# SpaStroWi_V1_R0.net
KiCad netlist of a schematic drawn in EAGLE
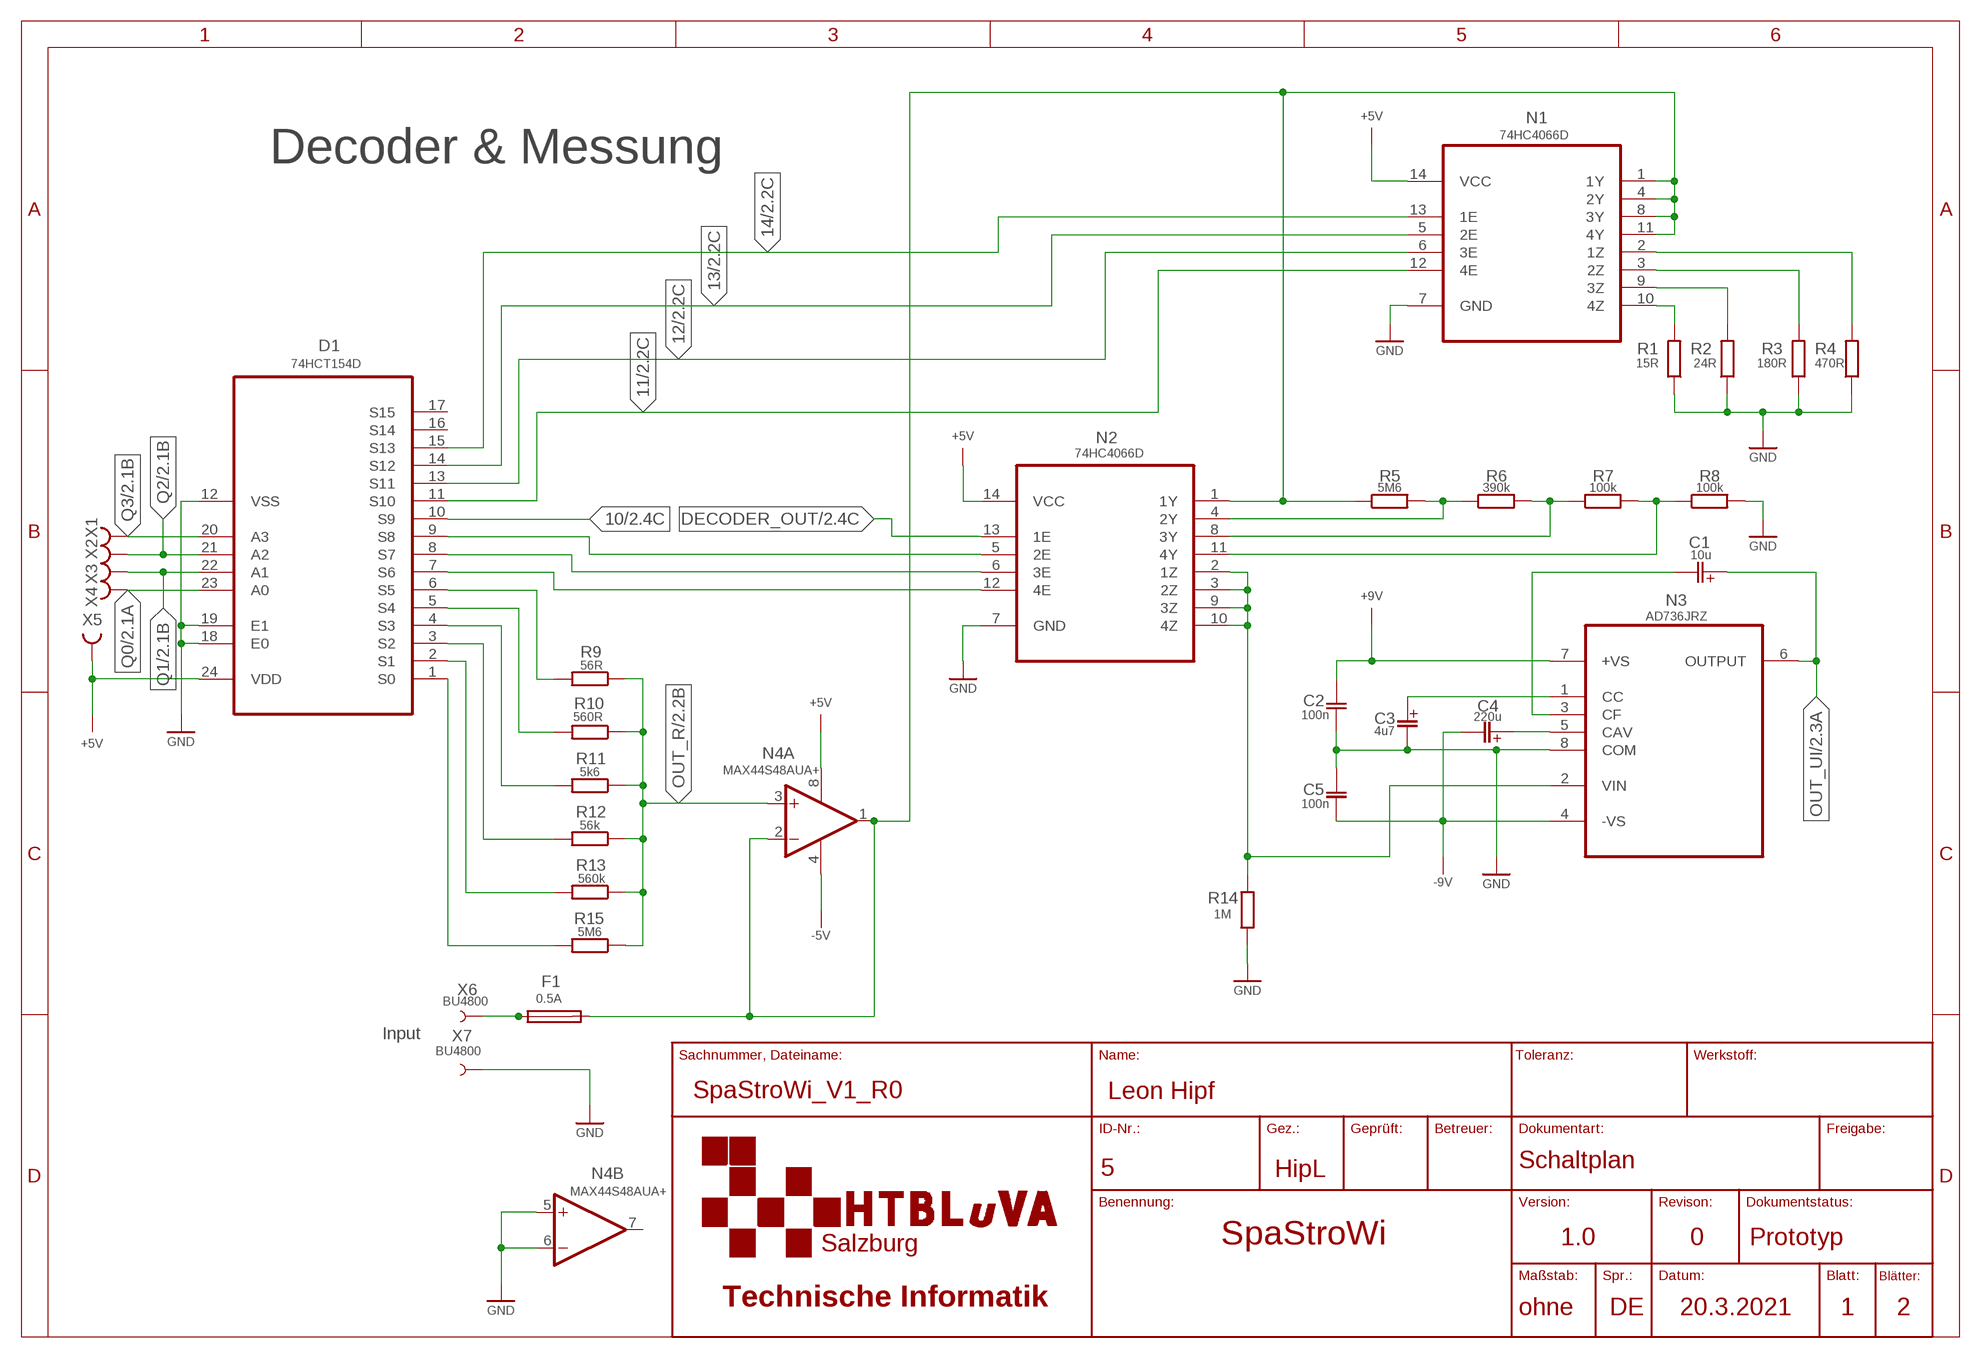
[diagram p0: schematic, sheet 1]
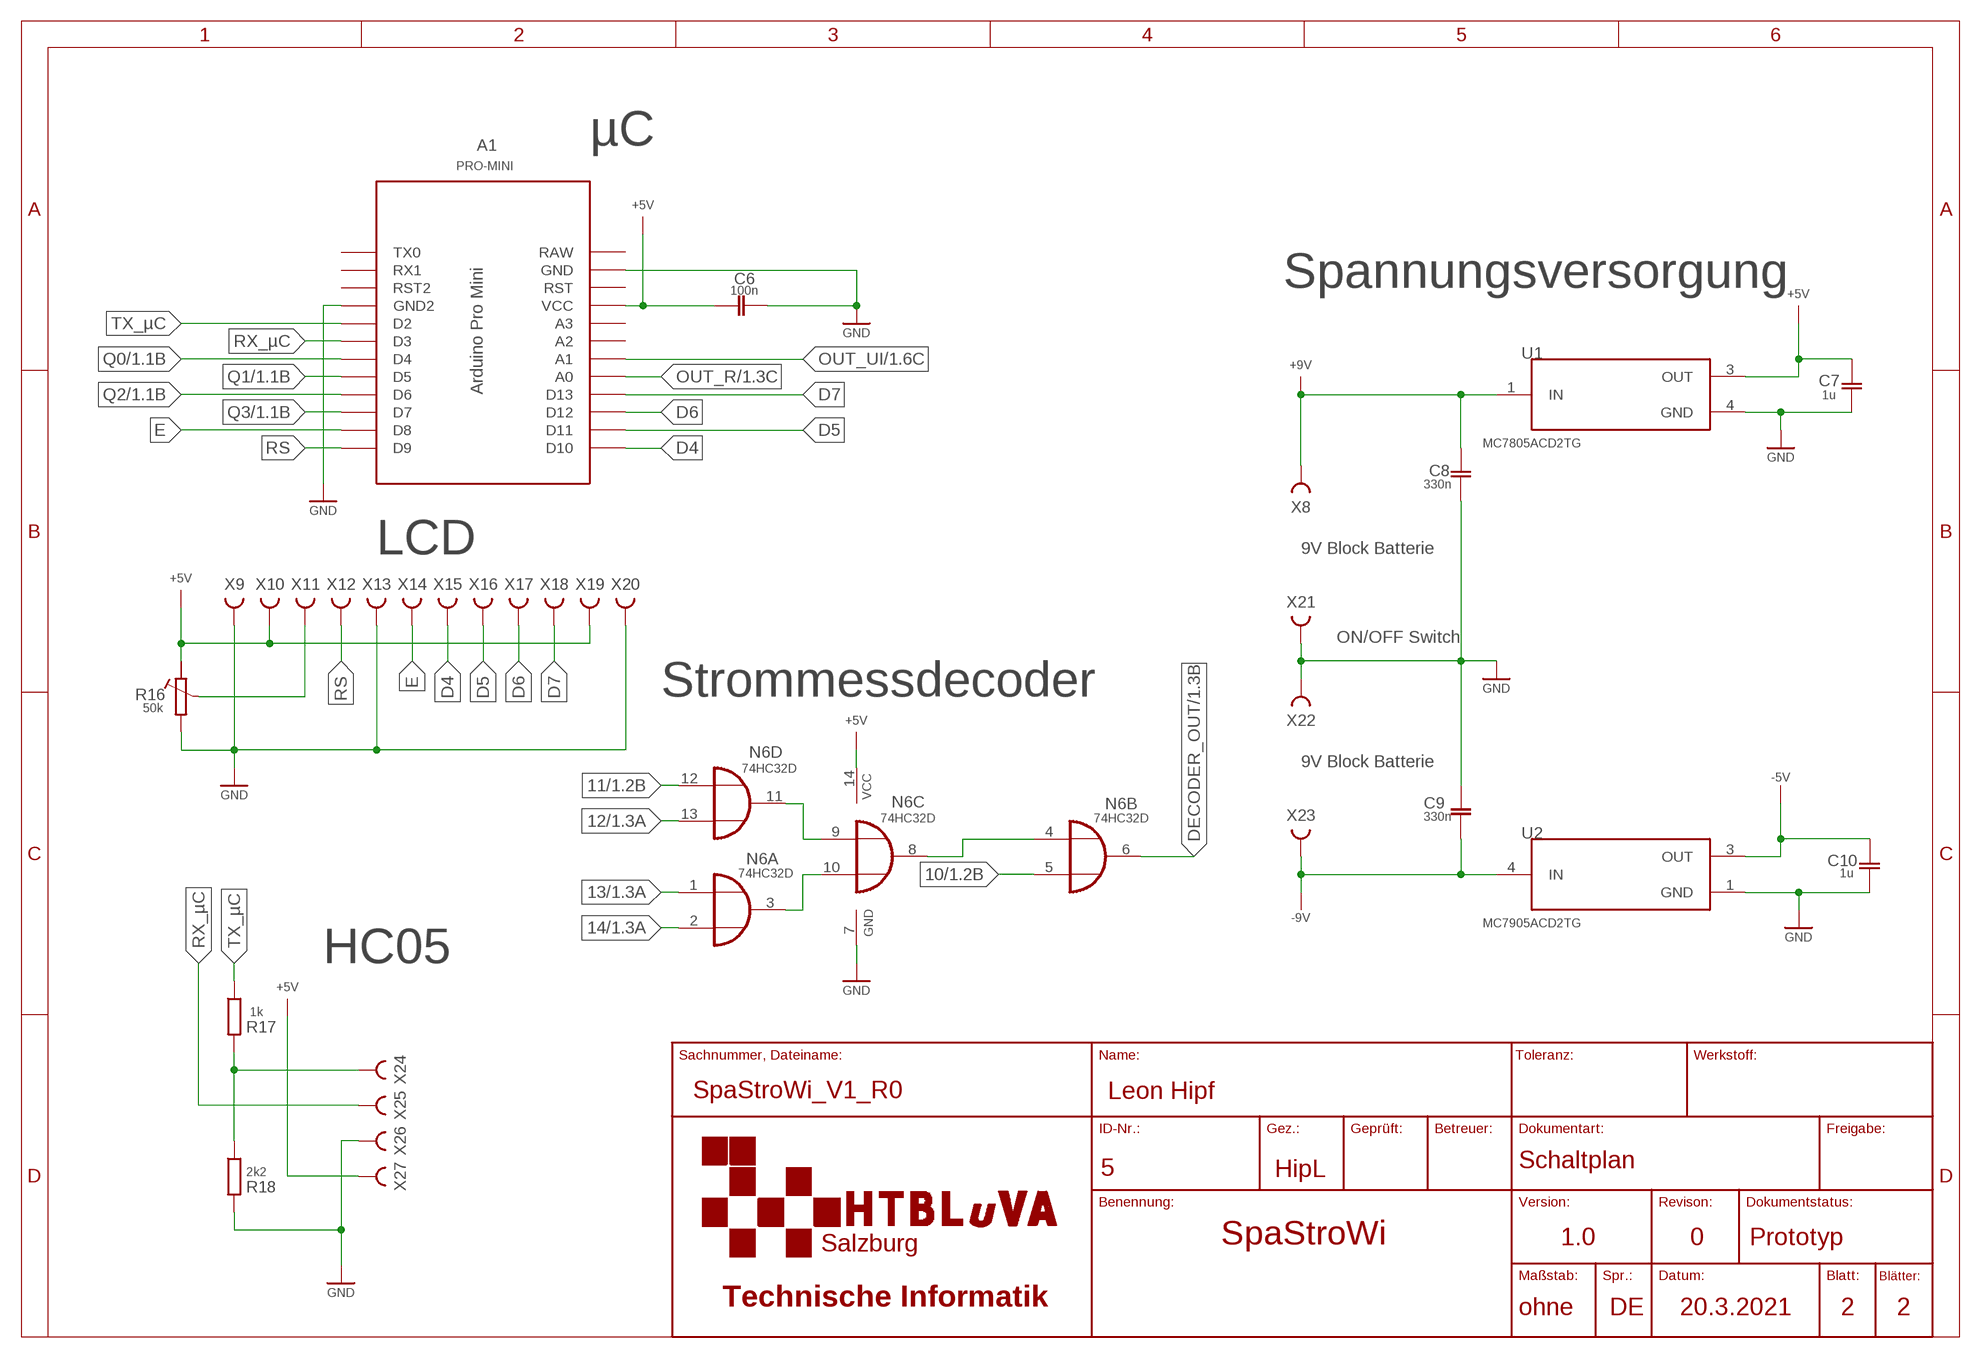
[diagram p1: schematic, sheet 2]

(export (version "E")
  (design (tool "Eeschema 10.0.6"))
  (components
    (comp (ref "C1")
      (value "10u")
      (footprint "eagle-import:153CLV-0405")
      (libsource (lib "eagle-import") (part "CPOL-EU153CLV-0405"))
    )
    (comp (ref "C2")
      (value "100n")
      (footprint "eagle-import:C0805")
      (libsource (lib "eagle-import") (part "C-EUC0805"))
    )
    (comp (ref "C3")
      (value "4u7")
      (footprint "eagle-import:153CLV-0405")
      (libsource (lib "eagle-import") (part "CPOL-EU153CLV-0405"))
    )
    (comp (ref "C4")
      (value "220u")
      (footprint "eagle-import:153CLV-0405")
      (libsource (lib "eagle-import") (part "CPOL-EU153CLV-0405"))
    )
    (comp (ref "C5")
      (value "100n")
      (footprint "eagle-import:C0805")
      (libsource (lib "eagle-import") (part "C-EUC0805"))
    )
    (comp (ref "D1")
      (value "74HCT154D")
      (footprint "eagle-import:SOIC127P1030X265-24N")
      (libsource (lib "eagle-import") (part "74HCT154D"))
    )
    (comp (ref "F1")
      (value "0.5A")
      (footprint "eagle-import:354-0101ZXGY")
      (libsource (lib "eagle-import") (part "0.5A"))
    )
    (comp (ref "N1")
      (value "74HC4066D")
      (footprint "eagle-import:SOIC127P600X175-14N")
      (fields (field (name "MF") "Nexperia") (field (name "MP") "74HC4066D,653"))
      (libsource (lib "eagle-import") (part "74HC4066D,653"))
    )
    (comp (ref "N2")
      (value "74HC4066D")
      (footprint "eagle-import:SOIC127P600X175-14N")
      (fields (field (name "MF") "Nexperia") (field (name "MP") "74HC4066D,653"))
      (libsource (lib "eagle-import") (part "74HC4066D,653"))
    )
    (comp (ref "N3")
      (value "AD736JRZ")
      (footprint "eagle-import:DIP794W45P254L959H508Q8")
      (libsource (lib "eagle-import") (part "AD736JRZ_THT"))
    )
    (comp (ref "N4")
      (value "MAX44S48AUA+")
      (footprint "eagle-import:SOP65P490X110-8N")
      (libsource (lib "eagle-import") (part "MAX44S48AUA+"))
    )
    (comp (ref "R1")
      (value "15R")
      (footprint "eagle-import:R2010")
      (libsource (lib "eagle-import") (part "R-EU_R2010"))
    )
    (comp (ref "R2")
      (value "24R")
      (footprint "eagle-import:R2512")
      (libsource (lib "eagle-import") (part "R-EU_R2512"))
    )
    (comp (ref "R3")
      (value "180R")
      (footprint "eagle-import:R0402")
      (libsource (lib "eagle-import") (part "R-EU_R0402"))
    )
    (comp (ref "R4")
      (value "470R")
      (footprint "eagle-import:R0805")
      (libsource (lib "eagle-import") (part "R-EU_R0805"))
    )
    (comp (ref "R5")
      (value "5M6")
      (footprint "eagle-import:R0805")
      (libsource (lib "eagle-import") (part "R-EU_R0805"))
    )
    (comp (ref "R6")
      (value "390k")
      (footprint "eagle-import:R0805")
      (libsource (lib "eagle-import") (part "R-EU_R0805"))
    )
    (comp (ref "R7")
      (value "100k")
      (footprint "eagle-import:R0805")
      (libsource (lib "eagle-import") (part "R-EU_R0805"))
    )
    (comp (ref "R8")
      (value "100k")
      (footprint "eagle-import:R0805")
      (libsource (lib "eagle-import") (part "R-EU_R0805"))
    )
    (comp (ref "R9")
      (value "56R")
      (footprint "eagle-import:R0805")
      (libsource (lib "eagle-import") (part "R-EU_R0805"))
    )
    (comp (ref "R10")
      (value "560R")
      (footprint "eagle-import:R0805")
      (libsource (lib "eagle-import") (part "R-EU_R0805"))
    )
    (comp (ref "R11")
      (value "5k6")
      (footprint "eagle-import:R0805")
      (libsource (lib "eagle-import") (part "R-EU_R0805"))
    )
    (comp (ref "R12")
      (value "56k")
      (footprint "eagle-import:R0805")
      (libsource (lib "eagle-import") (part "R-EU_R0805"))
    )
    (comp (ref "R13")
      (value "560k")
      (footprint "eagle-import:R0805")
      (libsource (lib "eagle-import") (part "R-EU_R0805"))
    )
    (comp (ref "R14")
      (value "1M")
      (footprint "eagle-import:R0805")
      (libsource (lib "eagle-import") (part "R-EU_R0805"))
    )
    (comp (ref "R15")
      (value "5M6")
      (footprint "eagle-import:R0805")
      (libsource (lib "eagle-import") (part "R-EU_R0805"))
    )
    (comp (ref "X1")
      (value "BUCHSE-V_0.8MM")
      (footprint "eagle-import:LSP08")
      (libsource (lib "eagle-import") (part "BUCHSE-V_0.8MM"))
    )
    (comp (ref "X2")
      (value "BUCHSE-V_0.8MM")
      (footprint "eagle-import:LSP08")
      (libsource (lib "eagle-import") (part "BUCHSE-V_0.8MM"))
    )
    (comp (ref "X3")
      (value "BUCHSE-V_0.8MM")
      (footprint "eagle-import:LSP08")
      (libsource (lib "eagle-import") (part "BUCHSE-V_0.8MM"))
    )
    (comp (ref "X4")
      (value "BUCHSE-V_0.8MM")
      (footprint "eagle-import:LSP08")
      (libsource (lib "eagle-import") (part "BUCHSE-V_0.8MM"))
    )
    (comp (ref "X5")
      (value "BUCHSE-V_0.8MM")
      (footprint "eagle-import:LSP08")
      (libsource (lib "eagle-import") (part "BUCHSE-V_0.8MM"))
    )
    (comp (ref "X6")
      (value "BU4800")
      (footprint "eagle-import:BU4800")
      (libsource (lib "eagle-import") (part "BU4800"))
    )
    (comp (ref "X7")
      (value "BU4800")
      (footprint "eagle-import:BU4800")
      (libsource (lib "eagle-import") (part "BU4800"))
    )
    (comp (ref "A1")
      (value "PRO-MINI")
      (footprint "eagle-import:PRO-MINI")
      (libsource (lib "eagle-import") (part "PRO-MINI"))
    )
    (comp (ref "C6")
      (value "100n")
      (footprint "eagle-import:C0805")
      (libsource (lib "eagle-import") (part "C-EUC0805"))
    )
    (comp (ref "C7")
      (value "1u")
      (footprint "eagle-import:C0805")
      (libsource (lib "eagle-import") (part "C-EUC0805"))
    )
    (comp (ref "C8")
      (value "330n")
      (footprint "eagle-import:C0805")
      (libsource (lib "eagle-import") (part "C-EUC0805"))
    )
    (comp (ref "C9")
      (value "330n")
      (footprint "eagle-import:C0805")
      (libsource (lib "eagle-import") (part "C-EUC0805"))
    )
    (comp (ref "C10")
      (value "1u")
      (footprint "eagle-import:C0805")
      (libsource (lib "eagle-import") (part "C-EUC0805"))
    )
    (comp (ref "N6")
      (value "74HC32D")
      (footprint "eagle-import:SO14")
      (libsource (lib "eagle-import") (part "7432DHC"))
    )
    (comp (ref "R16")
      (value "50k")
      (footprint "eagle-import:PTV09")
      (libsource (lib "eagle-import") (part "R-TRIMMPTV09"))
    )
    (comp (ref "R17")
      (value "1k")
      (footprint "eagle-import:R0805")
      (libsource (lib "eagle-import") (part "R-EU_R0805"))
    )
    (comp (ref "R18")
      (value "2k2")
      (footprint "eagle-import:R0805")
      (libsource (lib "eagle-import") (part "R-EU_R0805"))
    )
    (comp (ref "U1")
      (value "MC7805ACD2TG")
      (footprint "eagle-import:TO254P1420X457-3N")
      (fields (field (name "MF") "ON Semiconductor"))
      (libsource (lib "eagle-import") (part "MC7805ACD2TG"))
    )
    (comp (ref "U2")
      (value "MC7905ACD2TG")
      (footprint "eagle-import:TO254P1420X457-3N")
      (fields (field (name "MF") "ON Semiconductor") (field (name "MP") "MC7805ACD2TG"))
      (libsource (lib "eagle-import") (part "MC7905ACD2TG"))
    )
    (comp (ref "X8")
      (value "BUCHSE-V_0.8MM")
      (footprint "eagle-import:LSP08")
      (libsource (lib "eagle-import") (part "BUCHSE-V_0.8MM"))
    )
    (comp (ref "X9")
      (value "BUCHSE-V_0.8MM")
      (footprint "eagle-import:LSP08")
      (libsource (lib "eagle-import") (part "BUCHSE-V_0.8MM"))
    )
    (comp (ref "X10")
      (value "BUCHSE-V_0.8MM")
      (footprint "eagle-import:LSP08")
      (libsource (lib "eagle-import") (part "BUCHSE-V_0.8MM"))
    )
    (comp (ref "X11")
      (value "BUCHSE-V_0.8MM")
      (footprint "eagle-import:LSP08")
      (libsource (lib "eagle-import") (part "BUCHSE-V_0.8MM"))
    )
    (comp (ref "X12")
      (value "BUCHSE-V_0.8MM")
      (footprint "eagle-import:LSP08")
      (libsource (lib "eagle-import") (part "BUCHSE-V_0.8MM"))
    )
    (comp (ref "X13")
      (value "BUCHSE-V_0.8MM")
      (footprint "eagle-import:LSP08")
      (libsource (lib "eagle-import") (part "BUCHSE-V_0.8MM"))
    )
    (comp (ref "X14")
      (value "BUCHSE-V_0.8MM")
      (footprint "eagle-import:LSP08")
      (libsource (lib "eagle-import") (part "BUCHSE-V_0.8MM"))
    )
    (comp (ref "X15")
      (value "BUCHSE-V_0.8MM")
      (footprint "eagle-import:LSP08")
      (libsource (lib "eagle-import") (part "BUCHSE-V_0.8MM"))
    )
    (comp (ref "X16")
      (value "BUCHSE-V_0.8MM")
      (footprint "eagle-import:LSP08")
      (libsource (lib "eagle-import") (part "BUCHSE-V_0.8MM"))
    )
    (comp (ref "X17")
      (value "BUCHSE-V_0.8MM")
      (footprint "eagle-import:LSP08")
      (libsource (lib "eagle-import") (part "BUCHSE-V_0.8MM"))
    )
    (comp (ref "X18")
      (value "BUCHSE-V_0.8MM")
      (footprint "eagle-import:LSP08")
      (libsource (lib "eagle-import") (part "BUCHSE-V_0.8MM"))
    )
    (comp (ref "X19")
      (value "BUCHSE-V_0.8MM")
      (footprint "eagle-import:LSP08")
      (libsource (lib "eagle-import") (part "BUCHSE-V_0.8MM"))
    )
    (comp (ref "X20")
      (value "BUCHSE-V_0.8MM")
      (footprint "eagle-import:LSP08")
      (libsource (lib "eagle-import") (part "BUCHSE-V_0.8MM"))
    )
    (comp (ref "X21")
      (value "BUCHSE-V_0.8MM")
      (footprint "eagle-import:LSP08")
      (libsource (lib "eagle-import") (part "BUCHSE-V_0.8MM"))
    )
    (comp (ref "X22")
      (value "BUCHSE-V_0.8MM")
      (footprint "eagle-import:LSP08")
      (libsource (lib "eagle-import") (part "BUCHSE-V_0.8MM"))
    )
    (comp (ref "X23")
      (value "BUCHSE-V_0.8MM")
      (footprint "eagle-import:LSP08")
      (libsource (lib "eagle-import") (part "BUCHSE-V_0.8MM"))
    )
    (comp (ref "X24")
      (value "BUCHSE-V_0.8MM")
      (footprint "eagle-import:LSP08")
      (libsource (lib "eagle-import") (part "BUCHSE-V_0.8MM"))
    )
    (comp (ref "X25")
      (value "BUCHSE-V_0.8MM")
      (footprint "eagle-import:LSP08")
      (libsource (lib "eagle-import") (part "BUCHSE-V_0.8MM"))
    )
    (comp (ref "X26")
      (value "BUCHSE-V_0.8MM")
      (footprint "eagle-import:LSP08")
      (libsource (lib "eagle-import") (part "BUCHSE-V_0.8MM"))
    )
    (comp (ref "X27")
      (value "BUCHSE-V_0.8MM")
      (footprint "eagle-import:LSP08")
      (libsource (lib "eagle-import") (part "BUCHSE-V_0.8MM"))
    )
  )
  (nets
    (net (code "1") (name "+5V") (class "Default")
      (node (ref "A1") (pin "VCC") (pinfunction "VCC_VCC") (pintype "bidirectional"))
      (node (ref "C6") (pin "1") (pinfunction "1_1") (pintype "passive"))
      (node (ref "C7") (pin "1") (pinfunction "1_1") (pintype "passive"))
      (node (ref "D1") (pin "24") (pinfunction "VDD_24") (pintype "power_in"))
      (node (ref "N1") (pin "14") (pinfunction "VCC_14") (pintype "power_in"))
      (node (ref "N2") (pin "14") (pinfunction "VCC_14") (pintype "power_in"))
      (node (ref "N4") (pin "8") (pinfunction "VCC+_8") (pintype "power_in"))
      (node (ref "N6") (pin "14") (pinfunction "VCC_14") (pintype "power_in"))
      (node (ref "R16") (pin "1") (pinfunction "E_1") (pintype "passive"))
      (node (ref "U1") (pin "3") (pinfunction "OUT_3") (pintype "power_in"))
      (node (ref "X10") (pin "MP") (pinfunction "MP_MP") (pintype "passive"))
      (node (ref "X19") (pin "MP") (pinfunction "MP_MP") (pintype "passive"))
      (node (ref "X27") (pin "MP") (pinfunction "MP_MP") (pintype "passive"))
      (node (ref "X5") (pin "MP") (pinfunction "MP_MP") (pintype "passive"))
    )
    (net (code "2") (name "+9V") (class "Default")
      (node (ref "C2") (pin "1") (pinfunction "1_1") (pintype "passive"))
      (node (ref "C8") (pin "2") (pinfunction "2_2") (pintype "passive"))
      (node (ref "N3") (pin "7") (pinfunction "+VS_7") (pintype "power_in"))
      (node (ref "U1") (pin "1") (pinfunction "IN_1") (pintype "input"))
      (node (ref "X8") (pin "MP") (pinfunction "MP_MP") (pintype "passive"))
    )
    (net (code "3") (name "-5V") (class "Default")
      (node (ref "C10") (pin "1") (pinfunction "1_1") (pintype "passive"))
      (node (ref "N4") (pin "4") (pinfunction "VCC-_4") (pintype "power_in"))
      (node (ref "U2") (pin "3") (pinfunction "OUT_3") (pintype "power_in"))
    )
    (net (code "4") (name "-9V") (class "Default")
      (node (ref "C4") (pin "-") (pinfunction "-_-") (pintype "passive"))
      (node (ref "C5") (pin "2") (pinfunction "2_2") (pintype "passive"))
      (node (ref "C9") (pin "1") (pinfunction "1_1") (pintype "passive"))
      (node (ref "N3") (pin "4") (pinfunction "-VS_4") (pintype "power_in"))
      (node (ref "U2") (pin "4") (pinfunction "IN_4") (pintype "input"))
      (node (ref "X23") (pin "MP") (pinfunction "MP_MP") (pintype "passive"))
    )
    (net (code "5") (name "10") (class "Default")
      (node (ref "D1") (pin "10") (pinfunction "S9_10") (pintype "output"))
      (node (ref "N6") (pin "5") (pinfunction "I1_5") (pintype "input"))
    )
    (net (code "6") (name "11") (class "Default")
      (node (ref "D1") (pin "11") (pinfunction "S10_11") (pintype "output"))
      (node (ref "N1") (pin "12") (pinfunction "4E_12") (pintype "input"))
      (node (ref "N6") (pin "12") (pinfunction "I0_12") (pintype "input"))
    )
    (net (code "7") (name "12") (class "Default")
      (node (ref "D1") (pin "13") (pinfunction "S11_13") (pintype "output"))
      (node (ref "N1") (pin "6") (pinfunction "3E_6") (pintype "input"))
      (node (ref "N6") (pin "13") (pinfunction "I1_13") (pintype "input"))
    )
    (net (code "8") (name "13") (class "Default")
      (node (ref "D1") (pin "14") (pinfunction "S12_14") (pintype "output"))
      (node (ref "N1") (pin "5") (pinfunction "2E_5") (pintype "input"))
      (node (ref "N6") (pin "1") (pinfunction "I0_1") (pintype "input"))
    )
    (net (code "9") (name "14") (class "Default")
      (node (ref "D1") (pin "15") (pinfunction "S13_15") (pintype "output"))
      (node (ref "N1") (pin "13") (pinfunction "1E_13") (pintype "input"))
      (node (ref "N6") (pin "2") (pinfunction "I1_2") (pintype "input"))
    )
    (net (code "10") (name "D4") (class "Default")
      (node (ref "A1") (pin "D10") (pinfunction "D10_D10") (pintype "bidirectional"))
      (node (ref "X15") (pin "MP") (pinfunction "MP_MP") (pintype "passive"))
    )
    (net (code "11") (name "D5") (class "Default")
      (node (ref "A1") (pin "D11") (pinfunction "D11_D11") (pintype "bidirectional"))
      (node (ref "X16") (pin "MP") (pinfunction "MP_MP") (pintype "passive"))
    )
    (net (code "12") (name "D6") (class "Default")
      (node (ref "A1") (pin "D12") (pinfunction "D12_D12") (pintype "bidirectional"))
      (node (ref "X17") (pin "MP") (pinfunction "MP_MP") (pintype "passive"))
    )
    (net (code "13") (name "D7") (class "Default")
      (node (ref "A1") (pin "D13") (pinfunction "D13_D13") (pintype "bidirectional"))
      (node (ref "X18") (pin "MP") (pinfunction "MP_MP") (pintype "passive"))
    )
    (net (code "14") (name "DECODER_OUT") (class "Default")
      (node (ref "N2") (pin "13") (pinfunction "1E_13") (pintype "input"))
      (node (ref "N6") (pin "6") (pinfunction "O_6") (pintype "output"))
    )
    (net (code "15") (name "E") (class "Default")
      (node (ref "A1") (pin "D8") (pinfunction "D8_D8") (pintype "bidirectional"))
      (node (ref "X14") (pin "MP") (pinfunction "MP_MP") (pintype "passive"))
    )
    (net (code "16") (name "GND") (class "Default")
      (node (ref "A1") (pin "GND") (pinfunction "GND_GND") (pintype "input"))
      (node (ref "A1") (pin "GND1") (pinfunction "GND2_GND1") (pintype "bidirectional"))
      (node (ref "C10") (pin "2") (pinfunction "2_2") (pintype "passive"))
      (node (ref "C2") (pin "2") (pinfunction "2_2") (pintype "passive"))
      (node (ref "C3") (pin "-") (pinfunction "-_-") (pintype "passive"))
      (node (ref "C5") (pin "1") (pinfunction "1_1") (pintype "passive"))
      (node (ref "C6") (pin "2") (pinfunction "2_2") (pintype "passive"))
      (node (ref "C7") (pin "2") (pinfunction "2_2") (pintype "passive"))
      (node (ref "C8") (pin "1") (pinfunction "1_1") (pintype "passive"))
      (node (ref "C9") (pin "2") (pinfunction "2_2") (pintype "passive"))
      (node (ref "D1") (pin "12") (pinfunction "VSS_12") (pintype "power_in"))
      (node (ref "D1") (pin "18") (pinfunction "E0_18") (pintype "input"))
      (node (ref "D1") (pin "19") (pinfunction "E1_19") (pintype "input"))
      (node (ref "N1") (pin "7") (pinfunction "GND_7") (pintype "passive"))
      (node (ref "N2") (pin "7") (pinfunction "GND_7") (pintype "passive"))
      (node (ref "N3") (pin "8") (pinfunction "COM_8") (pintype "passive"))
      (node (ref "N4") (pin "5") (pinfunction "NON-INVERTING_INPUT2_5") (pintype "input"))
      (node (ref "N4") (pin "6") (pinfunction "INVERTING_INPUT2_6") (pintype "input"))
      (node (ref "N6") (pin "7") (pinfunction "GND_7") (pintype "power_in"))
      (node (ref "R1") (pin "1") (pinfunction "1_1") (pintype "passive"))
      (node (ref "R14") (pin "1") (pinfunction "1_1") (pintype "passive"))
      (node (ref "R16") (pin "3") (pinfunction "A_3") (pintype "passive"))
      (node (ref "R18") (pin "2") (pinfunction "2_2") (pintype "passive"))
      (node (ref "R2") (pin "1") (pinfunction "1_1") (pintype "passive"))
      (node (ref "R3") (pin "1") (pinfunction "1_1") (pintype "passive"))
      (node (ref "R4") (pin "1") (pinfunction "1_1") (pintype "passive"))
      (node (ref "R8") (pin "2") (pinfunction "2_2") (pintype "passive"))
      (node (ref "U1") (pin "4") (pinfunction "GND_4") (pintype "power_in"))
      (node (ref "U2") (pin "1") (pinfunction "GND_1") (pintype "power_in"))
      (node (ref "X13") (pin "MP") (pinfunction "MP_MP") (pintype "passive"))
      (node (ref "X20") (pin "MP") (pinfunction "MP_MP") (pintype "passive"))
      (node (ref "X21") (pin "MP") (pinfunction "MP_MP") (pintype "passive"))
      (node (ref "X22") (pin "MP") (pinfunction "MP_MP") (pintype "passive"))
      (node (ref "X26") (pin "MP") (pinfunction "MP_MP") (pintype "passive"))
      (node (ref "X7") (pin "P$1") (pinfunction "KL_P$1") (pintype "passive"))
      (node (ref "X9") (pin "MP") (pinfunction "MP_MP") (pintype "passive"))
    )
    (net (code "17") (name "Net-(D1-S0)") (class "Default")
      (node (ref "D1") (pin "1") (pinfunction "S0_1") (pintype "output"))
      (node (ref "R15") (pin "2") (pinfunction "2_2") (pintype "passive"))
    )
    (net (code "18") (name "Net-(D1-S1)") (class "Default")
      (node (ref "D1") (pin "2") (pinfunction "S1_2") (pintype "output"))
      (node (ref "R13") (pin "2") (pinfunction "2_2") (pintype "passive"))
    )
    (net (code "19") (name "Net-(D1-S2)") (class "Default")
      (node (ref "D1") (pin "3") (pinfunction "S2_3") (pintype "output"))
      (node (ref "R12") (pin "2") (pinfunction "2_2") (pintype "passive"))
    )
    (net (code "20") (name "Net-(D1-S3)") (class "Default")
      (node (ref "D1") (pin "4") (pinfunction "S3_4") (pintype "output"))
      (node (ref "R11") (pin "2") (pinfunction "2_2") (pintype "passive"))
    )
    (net (code "21") (name "Net-(D1-S4)") (class "Default")
      (node (ref "D1") (pin "5") (pinfunction "S4_5") (pintype "output"))
      (node (ref "R10") (pin "2") (pinfunction "2_2") (pintype "passive"))
    )
    (net (code "22") (name "Net-(D1-S5)") (class "Default")
      (node (ref "D1") (pin "6") (pinfunction "S5_6") (pintype "output"))
      (node (ref "R9") (pin "2") (pinfunction "2_2") (pintype "passive"))
    )
    (net (code "23") (name "Net-(D1-S6)") (class "Default")
      (node (ref "D1") (pin "7") (pinfunction "S6_7") (pintype "output"))
      (node (ref "N2") (pin "12") (pinfunction "4E_12") (pintype "input"))
    )
    (net (code "24") (name "Net-(D1-S7)") (class "Default")
      (node (ref "D1") (pin "8") (pinfunction "S7_8") (pintype "output"))
      (node (ref "N2") (pin "6") (pinfunction "3E_6") (pintype "input"))
    )
    (net (code "25") (name "Net-(D1-S8)") (class "Default")
      (node (ref "D1") (pin "9") (pinfunction "S8_9") (pintype "output"))
      (node (ref "N2") (pin "5") (pinfunction "2E_5") (pintype "input"))
    )
    (net (code "26") (name "Net-(N1-1Y)") (class "Default")
      (node (ref "F1") (pin "2") (pinfunction "2_2") (pintype "passive"))
      (node (ref "N1") (pin "1") (pinfunction "1Y_1") (pintype "bidirectional"))
      (node (ref "N1") (pin "11") (pinfunction "4Y_11") (pintype "bidirectional"))
      (node (ref "N1") (pin "4") (pinfunction "2Y_4") (pintype "bidirectional"))
      (node (ref "N1") (pin "8") (pinfunction "3Y_8") (pintype "bidirectional"))
      (node (ref "N2") (pin "1") (pinfunction "1Y_1") (pintype "bidirectional"))
      (node (ref "N4") (pin "1") (pinfunction "OUTPUT1_1") (pintype "output"))
      (node (ref "N4") (pin "2") (pinfunction "INVERTING_INPUT1_2") (pintype "input"))
      (node (ref "R5") (pin "1") (pinfunction "1_1") (pintype "passive"))
    )
    (net (code "27") (name "Net-(N1-1Z)") (class "Default")
      (node (ref "N1") (pin "2") (pinfunction "1Z_2") (pintype "bidirectional"))
      (node (ref "R4") (pin "2") (pinfunction "2_2") (pintype "passive"))
    )
    (net (code "28") (name "Net-(N1-2Z)") (class "Default")
      (node (ref "N1") (pin "3") (pinfunction "2Z_3") (pintype "bidirectional"))
      (node (ref "R3") (pin "2") (pinfunction "2_2") (pintype "passive"))
    )
    (net (code "29") (name "Net-(N1-3Z)") (class "Default")
      (node (ref "N1") (pin "9") (pinfunction "3Z_9") (pintype "bidirectional"))
      (node (ref "R2") (pin "2") (pinfunction "2_2") (pintype "passive"))
    )
    (net (code "30") (name "Net-(N1-4Z)") (class "Default")
      (node (ref "N1") (pin "10") (pinfunction "4Z_10") (pintype "bidirectional"))
      (node (ref "R1") (pin "2") (pinfunction "2_2") (pintype "passive"))
    )
    (net (code "31") (name "Net-(N2-1Z)") (class "Default")
      (node (ref "N2") (pin "10") (pinfunction "4Z_10") (pintype "bidirectional"))
      (node (ref "N2") (pin "2") (pinfunction "1Z_2") (pintype "bidirectional"))
      (node (ref "N2") (pin "3") (pinfunction "2Z_3") (pintype "bidirectional"))
      (node (ref "N2") (pin "9") (pinfunction "3Z_9") (pintype "bidirectional"))
      (node (ref "N3") (pin "2") (pinfunction "VIN_2") (pintype "input"))
      (node (ref "R14") (pin "2") (pinfunction "2_2") (pintype "passive"))
    )
    (net (code "32") (name "Net-(N2-2Y)") (class "Default")
      (node (ref "N2") (pin "4") (pinfunction "2Y_4") (pintype "bidirectional"))
      (node (ref "R5") (pin "2") (pinfunction "2_2") (pintype "passive"))
      (node (ref "R6") (pin "1") (pinfunction "1_1") (pintype "passive"))
    )
    (net (code "33") (name "Net-(N2-3Y)") (class "Default")
      (node (ref "N2") (pin "8") (pinfunction "3Y_8") (pintype "bidirectional"))
      (node (ref "R6") (pin "2") (pinfunction "2_2") (pintype "passive"))
      (node (ref "R7") (pin "1") (pinfunction "1_1") (pintype "passive"))
    )
    (net (code "34") (name "Net-(N2-4Y)") (class "Default")
      (node (ref "N2") (pin "11") (pinfunction "4Y_11") (pintype "bidirectional"))
      (node (ref "R7") (pin "2") (pinfunction "2_2") (pintype "passive"))
      (node (ref "R8") (pin "1") (pinfunction "1_1") (pintype "passive"))
    )
    (net (code "35") (name "Net-(N3-CAV)") (class "Default")
      (node (ref "C4") (pin "+") (pinfunction "+_+") (pintype "passive"))
      (node (ref "N3") (pin "5") (pinfunction "CAV_5") (pintype "passive"))
    )
    (net (code "36") (name "Net-(N3-CC)") (class "Default")
      (node (ref "C3") (pin "+") (pinfunction "+_+") (pintype "passive"))
      (node (ref "N3") (pin "1") (pinfunction "CC_1") (pintype "passive"))
    )
    (net (code "37") (name "Net-(N3-CF)") (class "Default")
      (node (ref "C1") (pin "-") (pinfunction "-_-") (pintype "passive"))
      (node (ref "N3") (pin "3") (pinfunction "CF_3") (pintype "passive"))
    )
    (net (code "38") (name "Net-(N6A-O)") (class "Default")
      (node (ref "N6") (pin "10") (pinfunction "I1_10") (pintype "input"))
      (node (ref "N6") (pin "3") (pinfunction "O_3") (pintype "output"))
    )
    (net (code "39") (name "Net-(N6B-I0)") (class "Default")
      (node (ref "N6") (pin "4") (pinfunction "I0_4") (pintype "input"))
      (node (ref "N6") (pin "8") (pinfunction "O_8") (pintype "output"))
    )
    (net (code "40") (name "Net-(N6C-I0)") (class "Default")
      (node (ref "N6") (pin "11") (pinfunction "O_11") (pintype "output"))
      (node (ref "N6") (pin "9") (pinfunction "I0_9") (pintype "input"))
    )
    (net (code "41") (name "Net-(R16-S)") (class "Default")
      (node (ref "R16") (pin "2") (pinfunction "S_2") (pintype "passive"))
      (node (ref "X11") (pin "MP") (pinfunction "MP_MP") (pintype "passive"))
    )
    (net (code "42") (name "Net-(R17-Pad2)") (class "Default")
      (node (ref "R17") (pin "2") (pinfunction "2_2") (pintype "passive"))
      (node (ref "R18") (pin "1") (pinfunction "1_1") (pintype "passive"))
      (node (ref "X24") (pin "MP") (pinfunction "MP_MP") (pintype "passive"))
    )
    (net (code "43") (name "Net-(X6-KL)") (class "Default")
      (node (ref "F1") (pin "1") (pinfunction "1_1") (pintype "passive"))
      (node (ref "X6") (pin "P$1") (pinfunction "KL_P$1") (pintype "passive"))
    )
    (net (code "44") (name "OUT_R") (class "Default")
      (node (ref "A1") (pin "A0") (pinfunction "A0_A0") (pintype "bidirectional"))
      (node (ref "N4") (pin "3") (pinfunction "NON-INVERTING_INPUT1_3") (pintype "input"))
      (node (ref "R10") (pin "1") (pinfunction "1_1") (pintype "passive"))
      (node (ref "R11") (pin "1") (pinfunction "1_1") (pintype "passive"))
      (node (ref "R12") (pin "1") (pinfunction "1_1") (pintype "passive"))
      (node (ref "R13") (pin "1") (pinfunction "1_1") (pintype "passive"))
      (node (ref "R15") (pin "1") (pinfunction "1_1") (pintype "passive"))
      (node (ref "R9") (pin "1") (pinfunction "1_1") (pintype "passive"))
    )
    (net (code "45") (name "OUT_UI") (class "Default")
      (node (ref "A1") (pin "A1") (pinfunction "A1_A1") (pintype "bidirectional"))
      (node (ref "C1") (pin "+") (pinfunction "+_+") (pintype "passive"))
      (node (ref "N3") (pin "6") (pinfunction "OUTPUT_6") (pintype "output"))
    )
    (net (code "46") (name "Q0") (class "Default")
      (node (ref "A1") (pin "D4") (pinfunction "D4_D4") (pintype "bidirectional"))
      (node (ref "D1") (pin "23") (pinfunction "A0_23") (pintype "input"))
      (node (ref "X4") (pin "MP") (pinfunction "MP_MP") (pintype "passive"))
    )
    (net (code "47") (name "Q1") (class "Default")
      (node (ref "A1") (pin "D5") (pinfunction "D5_D5") (pintype "bidirectional"))
      (node (ref "D1") (pin "22") (pinfunction "A1_22") (pintype "input"))
      (node (ref "X3") (pin "MP") (pinfunction "MP_MP") (pintype "passive"))
    )
    (net (code "48") (name "Q2") (class "Default")
      (node (ref "A1") (pin "D6") (pinfunction "D6_D6") (pintype "bidirectional"))
      (node (ref "D1") (pin "21") (pinfunction "A2_21") (pintype "input"))
      (node (ref "X2") (pin "MP") (pinfunction "MP_MP") (pintype "passive"))
    )
    (net (code "49") (name "Q3") (class "Default")
      (node (ref "A1") (pin "D7") (pinfunction "D7_D7") (pintype "bidirectional"))
      (node (ref "D1") (pin "20") (pinfunction "A3_20") (pintype "input"))
      (node (ref "X1") (pin "MP") (pinfunction "MP_MP") (pintype "passive"))
    )
    (net (code "50") (name "RAW") (class "Default")
      (node (ref "A1") (pin "RAW") (pinfunction "RAW_RAW") (pintype "power_in"))
    )
    (net (code "51") (name "RS") (class "Default")
      (node (ref "A1") (pin "D9") (pinfunction "D9_D9") (pintype "bidirectional"))
      (node (ref "X12") (pin "MP") (pinfunction "MP_MP") (pintype "passive"))
    )
    (net (code "52") (name "RX_µC") (class "Default")
      (node (ref "A1") (pin "D3") (pinfunction "D3_D3") (pintype "bidirectional"))
      (node (ref "X25") (pin "MP") (pinfunction "MP_MP") (pintype "passive"))
    )
    (net (code "53") (name "TX_µC") (class "Default")
      (node (ref "A1") (pin "D2") (pinfunction "D2_D2") (pintype "bidirectional"))
      (node (ref "R17") (pin "1") (pinfunction "1_1") (pintype "passive"))
    )
    (net (code "54") (name "unconnected-(A1-PadA2)") (class "Default")
      (node (ref "A1") (pin "A2") (pinfunction "A2_A2") (pintype "bidirectional"))
    )
    (net (code "55") (name "unconnected-(A1-PadA3)") (class "Default")
      (node (ref "A1") (pin "A3") (pinfunction "A3_A3") (pintype "bidirectional"))
    )
    (net (code "56") (name "unconnected-(A1-PadRST)") (class "Default")
      (node (ref "A1") (pin "RST") (pinfunction "RST_RST") (pintype "bidirectional"))
    )
    (net (code "57") (name "unconnected-(A1-PadRX1)") (class "Default")
      (node (ref "A1") (pin "RX1") (pinfunction "RX1_RX1") (pintype "bidirectional"))
    )
    (net (code "58") (name "unconnected-(A1-PadTX0)") (class "Default")
      (node (ref "A1") (pin "TX0") (pinfunction "TX0_TX0") (pintype "bidirectional"))
    )
    (net (code "59") (name "unconnected-(A1-RST2-PadRST1)") (class "Default")
      (node (ref "A1") (pin "RST1") (pinfunction "RST2_RST1") (pintype "bidirectional"))
    )
    (net (code "60") (name "unconnected-(D1-S14-Pad16)") (class "Default")
      (node (ref "D1") (pin "16") (pinfunction "S14_16") (pintype "output"))
    )
    (net (code "61") (name "unconnected-(D1-S15-Pad17)") (class "Default")
      (node (ref "D1") (pin "17") (pinfunction "S15_17") (pintype "output"))
    )
    (net (code "62") (name "unconnected-(N4B-OUTPUT2-Pad7)") (class "Default")
      (node (ref "N4") (pin "7") (pinfunction "OUTPUT2_7") (pintype "output"))
    )
  )
)
